# mcu.net
KiCad netlist of a schematic drawn in Altium Designer
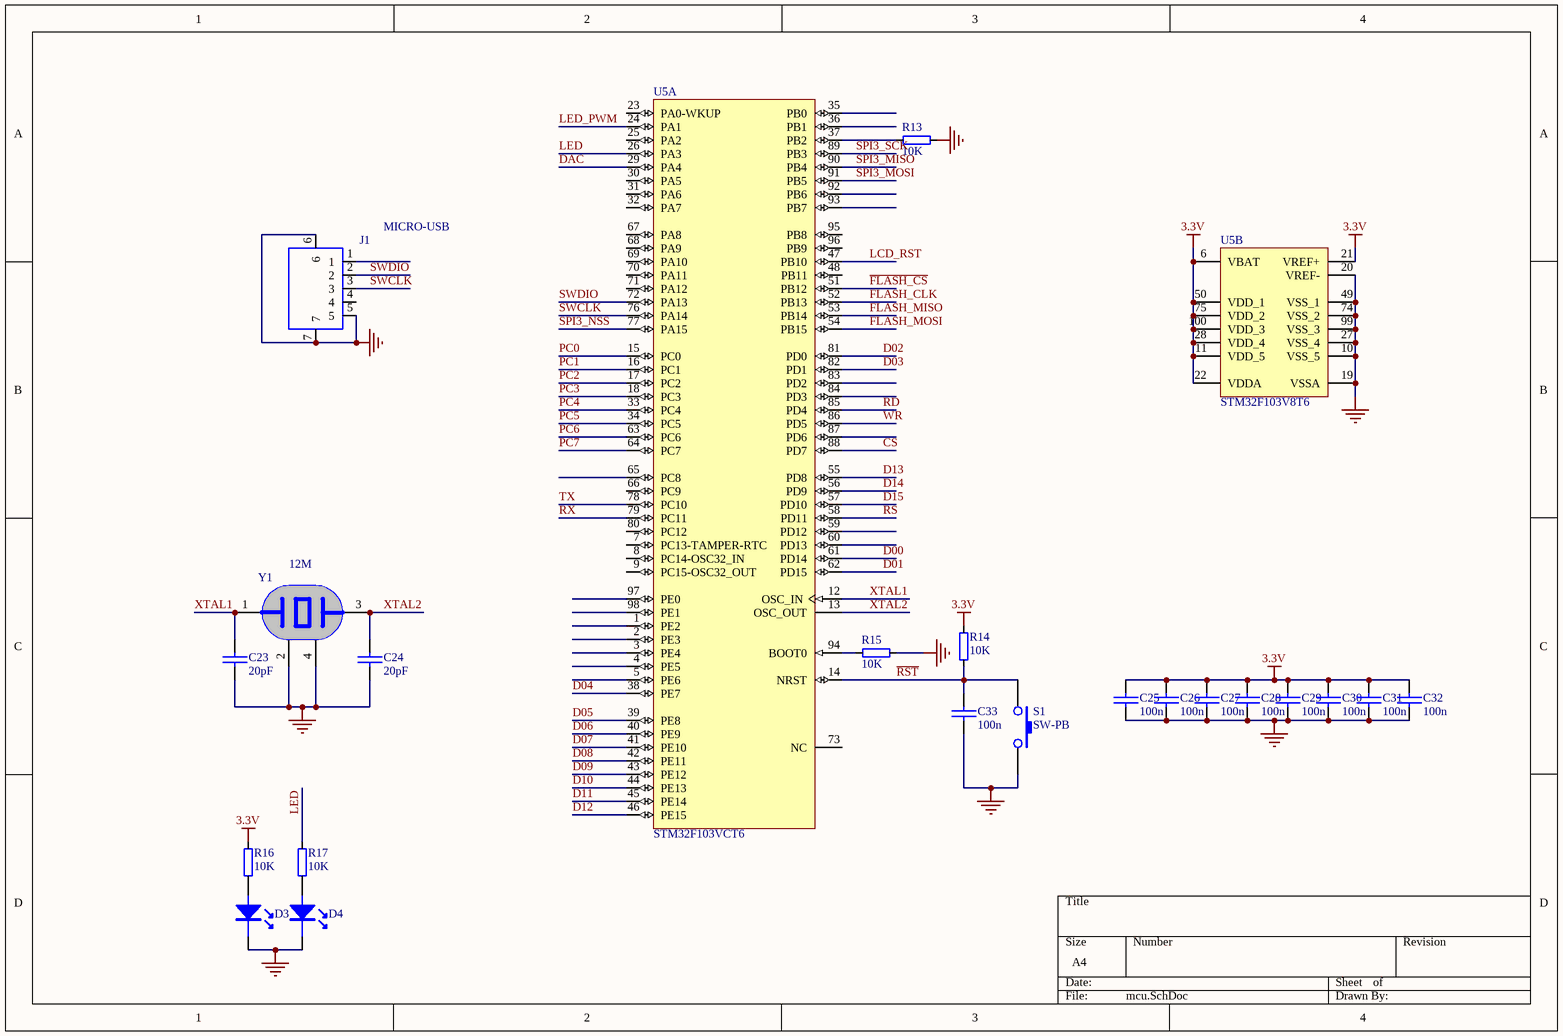
[diagram p0: mcu.SchDoc]

(export (version "E")
  (design (tool "Eeschema 10.0.6"))
  (components
    (comp (ref "C23")
      (value "20pF")
      (footprint "0603")
      (description "贴片瓷片电容")
      (libsource (lib "NCSchlib") (part "CAP"))
    )
    (comp (ref "C24")
      (value "20pF")
      (footprint "0603")
      (description "贴片瓷片电容")
      (libsource (lib "NCSchlib") (part "CAP"))
    )
    (comp (ref "C25")
      (value "100n")
      (footprint "0603")
      (description "贴片瓷片电容")
      (libsource (lib "NCSchlib") (part "CAP"))
    )
    (comp (ref "C26")
      (value "100n")
      (footprint "0603")
      (description "贴片瓷片电容")
      (libsource (lib "NCSchlib") (part "CAP"))
    )
    (comp (ref "C27")
      (value "100n")
      (footprint "0603")
      (description "贴片瓷片电容")
      (libsource (lib "NCSchlib") (part "CAP"))
    )
    (comp (ref "C28")
      (value "100n")
      (footprint "0603")
      (description "贴片瓷片电容")
      (libsource (lib "NCSchlib") (part "CAP"))
    )
    (comp (ref "C29")
      (value "100n")
      (footprint "0603")
      (description "贴片瓷片电容")
      (libsource (lib "NCSchlib") (part "CAP"))
    )
    (comp (ref "C30")
      (value "100n")
      (footprint "0603")
      (description "贴片瓷片电容")
      (libsource (lib "NCSchlib") (part "CAP"))
    )
    (comp (ref "C31")
      (value "100n")
      (footprint "0603")
      (description "贴片瓷片电容")
      (libsource (lib "NCSchlib") (part "CAP"))
    )
    (comp (ref "C32")
      (value "100n")
      (footprint "0603")
      (description "贴片瓷片电容")
      (libsource (lib "NCSchlib") (part "CAP"))
    )
    (comp (ref "C33")
      (value "100n")
      (footprint "0603")
      (description "贴片瓷片电容")
      (libsource (lib "NCSchlib") (part "CAP"))
    )
    (comp (ref "D3")
      (value "LED")
      (footprint "0603-LED")
      (description "贴片发光二极管")
      (libsource (lib "NCIntegrated_Library") (part "LED"))
    )
    (comp (ref "D4")
      (value "LED")
      (footprint "0603-LED")
      (description "贴片发光二极管")
      (libsource (lib "NCIntegrated_Library") (part "LED"))
    )
    (comp (ref "J1")
      (value "MICRO-USB")
      (footprint "MICRO-USB")
      (description "Micro USB插座")
      (libsource (lib "NCIntegrated_Library") (part "MICRO-USB"))
    )
    (comp (ref "R13")
      (value "10K")
      (footprint "0603")
      (description "贴片电阻（5%）")
      (libsource (lib "NCIntegrated_Library") (part "RES"))
    )
    (comp (ref "R14")
      (value "10K")
      (footprint "0603")
      (description "贴片电阻（5%）")
      (libsource (lib "NCIntegrated_Library") (part "RES"))
    )
    (comp (ref "R15")
      (value "10K")
      (footprint "0603")
      (description "贴片电阻（5%）")
      (libsource (lib "NCIntegrated_Library") (part "RES"))
    )
    (comp (ref "R16")
      (value "10K")
      (footprint "0603")
      (description "贴片电阻（5%）")
      (libsource (lib "NCIntegrated_Library") (part "RES"))
    )
    (comp (ref "R17")
      (value "10K")
      (footprint "0603")
      (description "贴片电阻（5%）")
      (libsource (lib "NCIntegrated_Library") (part "RES"))
    )
    (comp (ref "S1")
      (value "SW-PB")
      (footprint "KEY6*4")
      (description "按钮开关")
      (libsource (lib "NCIntegrated_Library") (part "SW-PB"))
    )
    (comp (ref "U5")
      (value "STM32F103VCT6")
      (footprint "STM-LQFP100_N")
      (fields (field (name "PARTNUMBER") "STM32F103V8T6"))
      (libsource (lib "STMicroelectronics STM32 F1") (part "STM32F103V8T6"))
    )
    (comp (ref "Y1")
      (value "12M")
      (footprint "XTAL-SMD3225")
      (description "晶振")
      (libsource (lib "NCIntegrated_Library") (part "XTAL4"))
    )
  )
  (nets
    (net (code "1") (name "/CS") (class "Default")
      (node (ref "U5") (pin "88") (pinfunction "PD7_88") (pintype "bidirectional"))
    )
    (net (code "2") (name "/D00") (class "Default")
      (node (ref "U5") (pin "61") (pinfunction "PD14_61") (pintype "bidirectional"))
    )
    (net (code "3") (name "/D01") (class "Default")
      (node (ref "U5") (pin "62") (pinfunction "PD15_62") (pintype "bidirectional"))
    )
    (net (code "4") (name "/D02") (class "Default")
      (node (ref "U5") (pin "81") (pinfunction "PD0_81") (pintype "bidirectional"))
    )
    (net (code "5") (name "/D03") (class "Default")
      (node (ref "U5") (pin "82") (pinfunction "PD1_82") (pintype "bidirectional"))
    )
    (net (code "6") (name "/D04") (class "Default")
      (node (ref "U5") (pin "38") (pinfunction "PE7_38") (pintype "bidirectional"))
    )
    (net (code "7") (name "/D05") (class "Default")
      (node (ref "U5") (pin "39") (pinfunction "PE8_39") (pintype "bidirectional"))
    )
    (net (code "8") (name "/D06") (class "Default")
      (node (ref "U5") (pin "40") (pinfunction "PE9_40") (pintype "bidirectional"))
    )
    (net (code "9") (name "/D07") (class "Default")
      (node (ref "U5") (pin "41") (pinfunction "PE10_41") (pintype "bidirectional"))
    )
    (net (code "10") (name "/D08") (class "Default")
      (node (ref "U5") (pin "42") (pinfunction "PE11_42") (pintype "bidirectional"))
    )
    (net (code "11") (name "/D09") (class "Default")
      (node (ref "U5") (pin "43") (pinfunction "PE12_43") (pintype "bidirectional"))
    )
    (net (code "12") (name "/D10") (class "Default")
      (node (ref "U5") (pin "44") (pinfunction "PE13_44") (pintype "bidirectional"))
    )
    (net (code "13") (name "/D11") (class "Default")
      (node (ref "U5") (pin "45") (pinfunction "PE14_45") (pintype "bidirectional"))
    )
    (net (code "14") (name "/D12") (class "Default")
      (node (ref "U5") (pin "46") (pinfunction "PE15_46") (pintype "bidirectional"))
    )
    (net (code "15") (name "/D13") (class "Default")
      (node (ref "U5") (pin "55") (pinfunction "PD8_55") (pintype "bidirectional"))
    )
    (net (code "16") (name "/D14") (class "Default")
      (node (ref "U5") (pin "56") (pinfunction "PD9_56") (pintype "bidirectional"))
    )
    (net (code "17") (name "/D15") (class "Default")
      (node (ref "U5") (pin "57") (pinfunction "PD10_57") (pintype "bidirectional"))
    )
    (net (code "18") (name "/DAC") (class "Default")
      (node (ref "U5") (pin "29") (pinfunction "PA4_29") (pintype "bidirectional"))
    )
    (net (code "19") (name "/FLASH_CLK") (class "Default")
      (node (ref "U5") (pin "52") (pinfunction "PB13_52") (pintype "bidirectional"))
    )
    (net (code "20") (name "/FLASH_MISO") (class "Default")
      (node (ref "U5") (pin "53") (pinfunction "PB14_53") (pintype "bidirectional"))
    )
    (net (code "21") (name "/FLASH_MOSI") (class "Default")
      (node (ref "U5") (pin "54") (pinfunction "PB15_54") (pintype "bidirectional"))
    )
    (net (code "22") (name "/LCD_RST") (class "Default")
      (node (ref "U5") (pin "47") (pinfunction "PB10_47") (pintype "bidirectional"))
    )
    (net (code "23") (name "/LED") (class "Default")
      (node (ref "R17") (pin "2") (pinfunction "2_2") (pintype "passive"))
      (node (ref "U5") (pin "26") (pinfunction "PA3_26") (pintype "bidirectional"))
    )
    (net (code "24") (name "/LED_PWM") (class "Default")
      (node (ref "U5") (pin "24") (pinfunction "PA1_24") (pintype "bidirectional"))
    )
    (net (code "25") (name "/PC0") (class "Default")
      (node (ref "U5") (pin "15") (pinfunction "PC0_15") (pintype "bidirectional"))
    )
    (net (code "26") (name "/PC1") (class "Default")
      (node (ref "U5") (pin "16") (pinfunction "PC1_16") (pintype "bidirectional"))
    )
    (net (code "27") (name "/PC2") (class "Default")
      (node (ref "U5") (pin "17") (pinfunction "PC2_17") (pintype "bidirectional"))
    )
    (net (code "28") (name "/PC3") (class "Default")
      (node (ref "U5") (pin "18") (pinfunction "PC3_18") (pintype "bidirectional"))
    )
    (net (code "29") (name "/PC4") (class "Default")
      (node (ref "U5") (pin "33") (pinfunction "PC4_33") (pintype "bidirectional"))
    )
    (net (code "30") (name "/PC5") (class "Default")
      (node (ref "U5") (pin "34") (pinfunction "PC5_34") (pintype "bidirectional"))
    )
    (net (code "31") (name "/PC6") (class "Default")
      (node (ref "U5") (pin "63") (pinfunction "PC6_63") (pintype "bidirectional"))
    )
    (net (code "32") (name "/PC7") (class "Default")
      (node (ref "U5") (pin "64") (pinfunction "PC7_64") (pintype "bidirectional"))
    )
    (net (code "33") (name "/RD") (class "Default")
      (node (ref "U5") (pin "85") (pinfunction "PD4_85") (pintype "bidirectional"))
    )
    (net (code "34") (name "/RS") (class "Default")
      (node (ref "U5") (pin "58") (pinfunction "PD11_58") (pintype "bidirectional"))
    )
    (net (code "35") (name "/RX") (class "Default")
      (node (ref "U5") (pin "79") (pinfunction "PC11_79") (pintype "bidirectional"))
    )
    (net (code "36") (name "/SPI3_MISO") (class "Default")
      (node (ref "U5") (pin "90") (pinfunction "PB4_90") (pintype "bidirectional"))
    )
    (net (code "37") (name "/SPI3_MOSI") (class "Default")
      (node (ref "U5") (pin "91") (pinfunction "PB5_91") (pintype "bidirectional"))
    )
    (net (code "38") (name "/SPI3_NSS") (class "Default")
      (node (ref "U5") (pin "77") (pinfunction "PA15_77") (pintype "bidirectional"))
    )
    (net (code "39") (name "/SPI3_SCK") (class "Default")
      (node (ref "U5") (pin "89") (pinfunction "PB3_89") (pintype "bidirectional"))
    )
    (net (code "40") (name "/SWCLK") (class "Default")
      (node (ref "J1") (pin "3") (pinfunction "3_3") (pintype "passive"))
      (node (ref "U5") (pin "76") (pinfunction "PA14_76") (pintype "bidirectional"))
    )
    (net (code "41") (name "/SWDIO") (class "Default")
      (node (ref "J1") (pin "2") (pinfunction "2_2") (pintype "passive"))
      (node (ref "U5") (pin "72") (pinfunction "PA13_72") (pintype "bidirectional"))
    )
    (net (code "42") (name "/TX") (class "Default")
      (node (ref "U5") (pin "78") (pinfunction "PC10_78") (pintype "bidirectional"))
    )
    (net (code "43") (name "/WR") (class "Default")
      (node (ref "U5") (pin "86") (pinfunction "PD5_86") (pintype "bidirectional"))
    )
    (net (code "44") (name "/XTAL1") (class "Default")
      (node (ref "C23") (pin "1") (pintype "passive"))
      (node (ref "U5") (pin "12") (pinfunction "OSC_IN_12") (pintype "input"))
      (node (ref "Y1") (pin "1") (pinfunction "1_1") (pintype "passive"))
    )
    (net (code "45") (name "/XTAL2") (class "Default")
      (node (ref "C24") (pin "1") (pintype "passive"))
      (node (ref "U5") (pin "13") (pinfunction "OSC_OUT_13") (pintype "passive"))
      (node (ref "Y1") (pin "3") (pinfunction "3_3") (pintype "passive"))
    )
    (net (code "46") (name "/~{FLASH_CS}") (class "Default")
      (node (ref "U5") (pin "51") (pinfunction "PB12_51") (pintype "bidirectional"))
    )
    (net (code "47") (name "/~{RST}") (class "Default")
      (node (ref "C33") (pin "1") (pintype "passive"))
      (node (ref "R14") (pin "1") (pinfunction "1_1") (pintype "passive"))
      (node (ref "S1") (pin "1") (pinfunction "1_1") (pintype "passive"))
      (node (ref "U5") (pin "14") (pinfunction "NRST_14") (pintype "bidirectional"))
    )
    (net (code "48") (name "3.3V") (class "Default")
      (node (ref "C25") (pin "1") (pintype "passive"))
      (node (ref "C26") (pin "1") (pintype "passive"))
      (node (ref "C27") (pin "1") (pintype "passive"))
      (node (ref "C28") (pin "1") (pintype "passive"))
      (node (ref "C29") (pin "1") (pintype "passive"))
      (node (ref "C30") (pin "1") (pintype "passive"))
      (node (ref "C31") (pin "1") (pintype "passive"))
      (node (ref "C32") (pin "1") (pintype "passive"))
      (node (ref "R14") (pin "2") (pinfunction "2_2") (pintype "passive"))
      (node (ref "R16") (pin "2") (pinfunction "2_2") (pintype "passive"))
      (node (ref "U5") (pin "100") (pinfunction "VDD_3_100") (pintype "power_in"))
      (node (ref "U5") (pin "11") (pinfunction "VDD_5_11") (pintype "power_in"))
      (node (ref "U5") (pin "21") (pinfunction "VREF+_21") (pintype "power_in"))
      (node (ref "U5") (pin "22") (pinfunction "VDDA_22") (pintype "power_in"))
      (node (ref "U5") (pin "28") (pinfunction "VDD_4_28") (pintype "power_in"))
      (node (ref "U5") (pin "50") (pinfunction "VDD_1_50") (pintype "power_in"))
      (node (ref "U5") (pin "6") (pinfunction "VBAT_6") (pintype "power_in"))
      (node (ref "U5") (pin "75") (pinfunction "VDD_2_75") (pintype "power_in"))
    )
    (net (code "49") (name "GND") (class "Default")
      (node (ref "C23") (pin "2") (pintype "passive"))
      (node (ref "C24") (pin "2") (pintype "passive"))
      (node (ref "C25") (pin "2") (pintype "passive"))
      (node (ref "C26") (pin "2") (pintype "passive"))
      (node (ref "C27") (pin "2") (pintype "passive"))
      (node (ref "C28") (pin "2") (pintype "passive"))
      (node (ref "C29") (pin "2") (pintype "passive"))
      (node (ref "C30") (pin "2") (pintype "passive"))
      (node (ref "C31") (pin "2") (pintype "passive"))
      (node (ref "C32") (pin "2") (pintype "passive"))
      (node (ref "C33") (pin "2") (pintype "passive"))
      (node (ref "D3") (pin "2") (pinfunction "K_2") (pintype "passive"))
      (node (ref "D4") (pin "2") (pinfunction "K_2") (pintype "passive"))
      (node (ref "J1") (pin "5") (pinfunction "5_5") (pintype "passive"))
      (node (ref "J1") (pin "6") (pinfunction "6_6") (pintype "passive"))
      (node (ref "J1") (pin "7") (pinfunction "7_7") (pintype "passive"))
      (node (ref "R13") (pin "2") (pinfunction "2_2") (pintype "passive"))
      (node (ref "R15") (pin "2") (pinfunction "2_2") (pintype "passive"))
      (node (ref "S1") (pin "2") (pinfunction "2_2") (pintype "passive"))
      (node (ref "U5") (pin "10") (pinfunction "VSS_5_10") (pintype "power_in"))
      (node (ref "U5") (pin "19") (pinfunction "VSSA_19") (pintype "power_in"))
      (node (ref "U5") (pin "20") (pinfunction "VREF-_20") (pintype "power_in"))
      (node (ref "U5") (pin "27") (pinfunction "VSS_4_27") (pintype "power_in"))
      (node (ref "U5") (pin "49") (pinfunction "VSS_1_49") (pintype "power_in"))
      (node (ref "U5") (pin "74") (pinfunction "VSS_2_74") (pintype "power_in"))
      (node (ref "U5") (pin "99") (pinfunction "VSS_3_99") (pintype "power_in"))
      (node (ref "Y1") (pin "2") (pinfunction "2_2") (pintype "passive"))
      (node (ref "Y1") (pin "4") (pinfunction "2_4") (pintype "passive"))
    )
    (net (code "50") (name "Net-(D3-A)") (class "Default")
      (node (ref "D3") (pin "1") (pinfunction "A_1") (pintype "passive"))
      (node (ref "R16") (pin "1") (pinfunction "1_1") (pintype "passive"))
    )
    (net (code "51") (name "Net-(D4-A)") (class "Default")
      (node (ref "D4") (pin "1") (pinfunction "A_1") (pintype "passive"))
      (node (ref "R17") (pin "1") (pinfunction "1_1") (pintype "passive"))
    )
    (net (code "52") (name "Net-(U5A-BOOT0)") (class "Default")
      (node (ref "R15") (pin "1") (pinfunction "1_1") (pintype "passive"))
      (node (ref "U5") (pin "94") (pinfunction "BOOT0_94") (pintype "input"))
    )
    (net (code "53") (name "Net-(U5A-PB2)") (class "Default")
      (node (ref "R13") (pin "1") (pinfunction "1_1") (pintype "passive"))
      (node (ref "U5") (pin "37") (pinfunction "PB2_37") (pintype "bidirectional"))
    )
    (net (code "54") (name "unconnected-(J1-Pad1)") (class "Default")
      (node (ref "J1") (pin "1") (pinfunction "1_1") (pintype "passive"))
    )
    (net (code "55") (name "unconnected-(J1-Pad4)") (class "Default")
      (node (ref "J1") (pin "4") (pinfunction "4_4") (pintype "passive"))
    )
    (net (code "56") (name "unconnected-(U5A-NC-Pad73)") (class "Default")
      (node (ref "U5") (pin "73") (pinfunction "NC_73") (pintype "passive"))
    )
    (net (code "57") (name "unconnected-(U5A-PA0-WKUP-Pad23)") (class "Default")
      (node (ref "U5") (pin "23") (pinfunction "PA0-WKUP_23") (pintype "bidirectional"))
    )
    (net (code "58") (name "unconnected-(U5A-PA2-Pad25)") (class "Default")
      (node (ref "U5") (pin "25") (pinfunction "PA2_25") (pintype "bidirectional"))
    )
    (net (code "59") (name "unconnected-(U5A-PA5-Pad30)") (class "Default")
      (node (ref "U5") (pin "30") (pinfunction "PA5_30") (pintype "bidirectional"))
    )
    (net (code "60") (name "unconnected-(U5A-PA6-Pad31)") (class "Default")
      (node (ref "U5") (pin "31") (pinfunction "PA6_31") (pintype "bidirectional"))
    )
    (net (code "61") (name "unconnected-(U5A-PA7-Pad32)") (class "Default")
      (node (ref "U5") (pin "32") (pinfunction "PA7_32") (pintype "bidirectional"))
    )
    (net (code "62") (name "unconnected-(U5A-PA8-Pad67)") (class "Default")
      (node (ref "U5") (pin "67") (pinfunction "PA8_67") (pintype "bidirectional"))
    )
    (net (code "63") (name "unconnected-(U5A-PA9-Pad68)") (class "Default")
      (node (ref "U5") (pin "68") (pinfunction "PA9_68") (pintype "bidirectional"))
    )
    (net (code "64") (name "unconnected-(U5A-PA10-Pad69)") (class "Default")
      (node (ref "U5") (pin "69") (pinfunction "PA10_69") (pintype "bidirectional"))
    )
    (net (code "65") (name "unconnected-(U5A-PA11-Pad70)") (class "Default")
      (node (ref "U5") (pin "70") (pinfunction "PA11_70") (pintype "bidirectional"))
    )
    (net (code "66") (name "unconnected-(U5A-PA12-Pad71)") (class "Default")
      (node (ref "U5") (pin "71") (pinfunction "PA12_71") (pintype "bidirectional"))
    )
    (net (code "67") (name "unconnected-(U5A-PB0-Pad35)") (class "Default")
      (node (ref "U5") (pin "35") (pinfunction "PB0_35") (pintype "bidirectional"))
    )
    (net (code "68") (name "unconnected-(U5A-PB1-Pad36)") (class "Default")
      (node (ref "U5") (pin "36") (pinfunction "PB1_36") (pintype "bidirectional"))
    )
    (net (code "69") (name "unconnected-(U5A-PB6-Pad92)") (class "Default")
      (node (ref "U5") (pin "92") (pinfunction "PB6_92") (pintype "bidirectional"))
    )
    (net (code "70") (name "unconnected-(U5A-PB7-Pad93)") (class "Default")
      (node (ref "U5") (pin "93") (pinfunction "PB7_93") (pintype "bidirectional"))
    )
    (net (code "71") (name "unconnected-(U5A-PB8-Pad95)") (class "Default")
      (node (ref "U5") (pin "95") (pinfunction "PB8_95") (pintype "bidirectional"))
    )
    (net (code "72") (name "unconnected-(U5A-PB9-Pad96)") (class "Default")
      (node (ref "U5") (pin "96") (pinfunction "PB9_96") (pintype "bidirectional"))
    )
    (net (code "73") (name "unconnected-(U5A-PB11-Pad48)") (class "Default")
      (node (ref "U5") (pin "48") (pinfunction "PB11_48") (pintype "bidirectional"))
    )
    (net (code "74") (name "unconnected-(U5A-PC8-Pad65)") (class "Default")
      (node (ref "U5") (pin "65") (pinfunction "PC8_65") (pintype "bidirectional"))
    )
    (net (code "75") (name "unconnected-(U5A-PC9-Pad66)") (class "Default")
      (node (ref "U5") (pin "66") (pinfunction "PC9_66") (pintype "bidirectional"))
    )
    (net (code "76") (name "unconnected-(U5A-PC12-Pad80)") (class "Default")
      (node (ref "U5") (pin "80") (pinfunction "PC12_80") (pintype "bidirectional"))
    )
    (net (code "77") (name "unconnected-(U5A-PC13-TAMPER-RTC-Pad7)") (class "Default")
      (node (ref "U5") (pin "7") (pinfunction "PC13-TAMPER-RTC_7") (pintype "bidirectional"))
    )
    (net (code "78") (name "unconnected-(U5A-PC14-OSC32_IN-Pad8)") (class "Default")
      (node (ref "U5") (pin "8") (pinfunction "PC14-OSC32_IN_8") (pintype "bidirectional"))
    )
    (net (code "79") (name "unconnected-(U5A-PC15-OSC32_OUT-Pad9)") (class "Default")
      (node (ref "U5") (pin "9") (pinfunction "PC15-OSC32_OUT_9") (pintype "bidirectional"))
    )
    (net (code "80") (name "unconnected-(U5A-PD2-Pad83)") (class "Default")
      (node (ref "U5") (pin "83") (pinfunction "PD2_83") (pintype "bidirectional"))
    )
    (net (code "81") (name "unconnected-(U5A-PD3-Pad84)") (class "Default")
      (node (ref "U5") (pin "84") (pinfunction "PD3_84") (pintype "bidirectional"))
    )
    (net (code "82") (name "unconnected-(U5A-PD6-Pad87)") (class "Default")
      (node (ref "U5") (pin "87") (pinfunction "PD6_87") (pintype "bidirectional"))
    )
    (net (code "83") (name "unconnected-(U5A-PD12-Pad59)") (class "Default")
      (node (ref "U5") (pin "59") (pinfunction "PD12_59") (pintype "bidirectional"))
    )
    (net (code "84") (name "unconnected-(U5A-PD13-Pad60)") (class "Default")
      (node (ref "U5") (pin "60") (pinfunction "PD13_60") (pintype "bidirectional"))
    )
    (net (code "85") (name "unconnected-(U5A-PE0-Pad97)") (class "Default")
      (node (ref "U5") (pin "97") (pinfunction "PE0_97") (pintype "bidirectional"))
    )
    (net (code "86") (name "unconnected-(U5A-PE1-Pad98)") (class "Default")
      (node (ref "U5") (pin "98") (pinfunction "PE1_98") (pintype "bidirectional"))
    )
    (net (code "87") (name "unconnected-(U5A-PE2-Pad1)") (class "Default")
      (node (ref "U5") (pin "1") (pinfunction "PE2_1") (pintype "bidirectional"))
    )
    (net (code "88") (name "unconnected-(U5A-PE3-Pad2)") (class "Default")
      (node (ref "U5") (pin "2") (pinfunction "PE3_2") (pintype "bidirectional"))
    )
    (net (code "89") (name "unconnected-(U5A-PE4-Pad3)") (class "Default")
      (node (ref "U5") (pin "3") (pinfunction "PE4_3") (pintype "bidirectional"))
    )
    (net (code "90") (name "unconnected-(U5A-PE5-Pad4)") (class "Default")
      (node (ref "U5") (pin "4") (pinfunction "PE5_4") (pintype "bidirectional"))
    )
    (net (code "91") (name "unconnected-(U5A-PE6-Pad5)") (class "Default")
      (node (ref "U5") (pin "5") (pinfunction "PE6_5") (pintype "bidirectional"))
    )
  )
)
